# Misc.net
KiCad netlist of a schematic drawn in Altium Designer
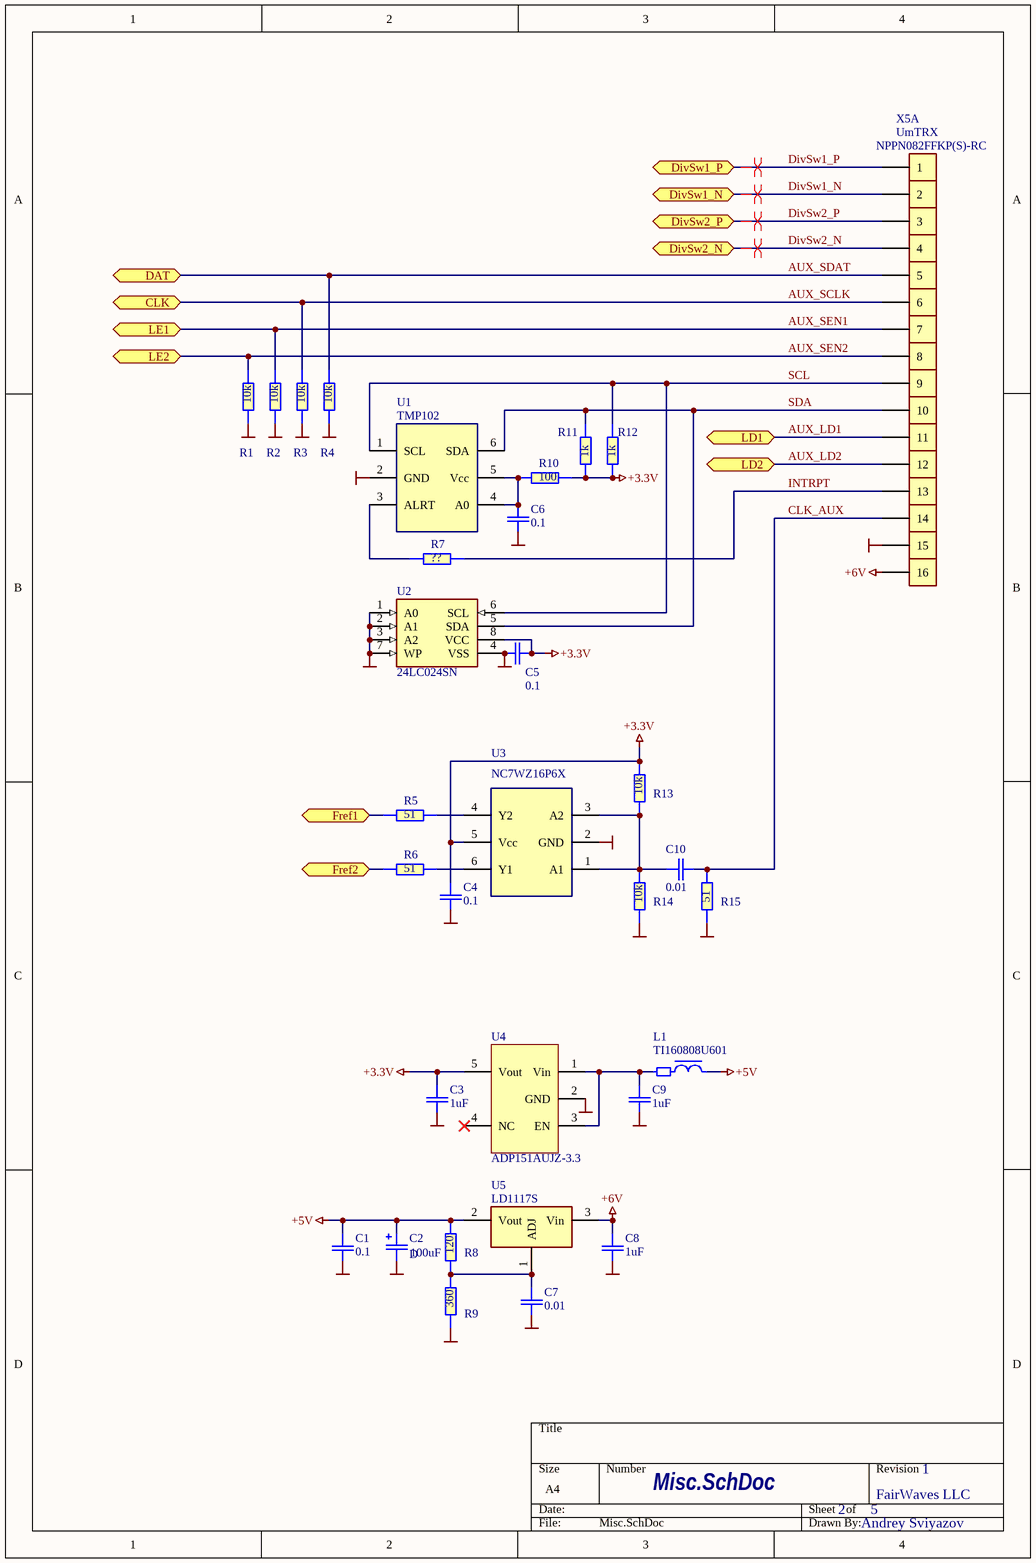
[diagram p0: Misc.SchDoc]

(export (version "E")
  (design (tool "Eeschema 10.0.6"))
  (components
    (comp (ref "C1")
      (value "0.1")
      (footprint "C0603-Phillips")
      (description "Capacitor")
      (fields (field (name "MANUFACTURER") "MURATA") (field (name "TOLERANCE") "20%"))
      (libsource (lib "Capacitors") (part "C0603"))
    )
    (comp (ref "C2")
      (value "100uF")
      (footprint "cd7343")
      (description "Capacitor")
      (fields (field (name "MANUFACTURER") "SPRAGUE"))
      (libsource (lib "altium-import") (part "root_0_mirrored_CD7343_"))
    )
    (comp (ref "C3")
      (value "1uF")
      (footprint "C0603-Phillips")
      (description "Capacitor")
      (fields (field (name "MANUFACTURER") "MURATA") (field (name "TOLERANCE") "20%"))
      (libsource (lib "Capacitors") (part "C0603"))
    )
    (comp (ref "C4")
      (value "0.1")
      (footprint "C0603-Phillips")
      (description "Capacitor")
      (fields (field (name "MANUFACTURER") "MURATA") (field (name "TOLERANCE") "20%"))
      (libsource (lib "Capacitors") (part "C0603"))
    )
    (comp (ref "C5")
      (value "0.1")
      (footprint "C0603-Phillips")
      (description "Capacitor")
      (fields (field (name "MANUFACTURER") "MURATA") (field (name "TOLERANCE") "20%"))
      (libsource (lib "Capacitors") (part "C0603"))
    )
    (comp (ref "C6")
      (value "0.1")
      (footprint "C0603-Phillips")
      (description "Capacitor")
      (fields (field (name "MANUFACTURER") "MURATA") (field (name "TOLERANCE") "20%"))
      (libsource (lib "Capacitors") (part "C0603"))
    )
    (comp (ref "C7")
      (value "0.01")
      (footprint "C0603-Phillips")
      (description "Capacitor")
      (fields (field (name "MANUFACTURER") "MURATA") (field (name "TOLERANCE") "20%"))
      (libsource (lib "Capacitors") (part "C0603"))
    )
    (comp (ref "C8")
      (value "1uF")
      (footprint "C0603-Phillips")
      (description "Capacitor")
      (fields (field (name "MANUFACTURER") "MURATA") (field (name "TOLERANCE") "20%"))
      (libsource (lib "Capacitors") (part "C0603"))
    )
    (comp (ref "C9")
      (value "1uF")
      (footprint "C0603-Phillips")
      (description "Capacitor")
      (fields (field (name "MANUFACTURER") "MURATA") (field (name "TOLERANCE") "20%"))
      (libsource (lib "Capacitors") (part "C0603"))
    )
    (comp (ref "C10")
      (value "0.01")
      (footprint "C0603-Phillips")
      (description "Capacitor")
      (fields (field (name "MANUFACTURER") "MURATA") (field (name "TOLERANCE") "20%"))
      (libsource (lib "Capacitors") (part "C0603"))
    )
    (comp (ref "L1")
      (value "TI160808U601")
      (footprint "Andy:Ti160808-Phillips")
      (description "Choke")
      (fields (field (name "MANUFACTURER") "MURATA"))
      (libsource (lib "altium-import") (part "root_0_mirrored_TI160808_"))
    )
    (comp (ref "R1")
      (value "10k")
      (footprint "R0603-PHILLIPS")
      (description "Resistor")
      (fields (field (name "MANUFACTURER") "YAGEO") (field (name "TOLERANCE") "5%"))
      (libsource (lib "altium-import") (part "root_2_R0603_"))
    )
    (comp (ref "R2")
      (value "10k")
      (footprint "R0603-PHILLIPS")
      (description "Resistor")
      (fields (field (name "MANUFACTURER") "YAGEO") (field (name "TOLERANCE") "5%"))
      (libsource (lib "altium-import") (part "root_2_R0603_"))
    )
    (comp (ref "R3")
      (value "10k")
      (footprint "R0603-PHILLIPS")
      (description "Resistor")
      (fields (field (name "MANUFACTURER") "YAGEO") (field (name "TOLERANCE") "5%"))
      (libsource (lib "altium-import") (part "root_2_R0603_"))
    )
    (comp (ref "R4")
      (value "10k")
      (footprint "R0603-PHILLIPS")
      (description "Resistor")
      (fields (field (name "MANUFACTURER") "YAGEO") (field (name "TOLERANCE") "5%"))
      (libsource (lib "altium-import") (part "root_2_R0603_"))
    )
    (comp (ref "R5")
      (value "51")
      (footprint "R0603-PHILLIPS")
      (description "Resistor")
      (fields (field (name "MANUFACTURER") "YAGEO") (field (name "TOLERANCE") "5%"))
      (libsource (lib "altium-import") (part "root_1_R0603_"))
    )
    (comp (ref "R6")
      (value "51")
      (footprint "R0603-PHILLIPS")
      (description "Resistor")
      (fields (field (name "MANUFACTURER") "YAGEO") (field (name "TOLERANCE") "5%"))
      (libsource (lib "altium-import") (part "root_1_R0603_"))
    )
    (comp (ref "R7")
      (value "??")
      (footprint "R0603-PHILLIPS")
      (description "Resistor")
      (fields (field (name "MANUFACTURER") "YAGEO") (field (name "TOLERANCE") "5%"))
      (libsource (lib "altium-import") (part "root_1_R0603_"))
    )
    (comp (ref "R8")
      (value "120")
      (footprint "R0603-PHILLIPS")
      (description "Resistor")
      (fields (field (name "MANUFACTURER") "YAGEO") (field (name "TOLERANCE") "5%"))
      (libsource (lib "altium-import") (part "root_0_mirrored_R0603_"))
    )
    (comp (ref "R9")
      (value "360")
      (footprint "R0603-PHILLIPS")
      (description "Resistor")
      (fields (field (name "MANUFACTURER") "YAGEO") (field (name "TOLERANCE") "5%"))
      (libsource (lib "altium-import") (part "root_0_mirrored_R0603_"))
    )
    (comp (ref "R10")
      (value "100")
      (footprint "R0603-PHILLIPS")
      (description "Resistor")
      (fields (field (name "MANUFACTURER") "YAGEO") (field (name "TOLERANCE") "5%"))
      (libsource (lib "altium-import") (part "root_1_R0603_"))
    )
    (comp (ref "R11")
      (value "1k")
      (footprint "R0603-PHILLIPS")
      (description "Resistor")
      (fields (field (name "MANUFACTURER") "YAGEO") (field (name "TOLERANCE") "5%"))
      (libsource (lib "altium-import") (part "root_2_R0603_"))
    )
    (comp (ref "R12")
      (value "1k")
      (footprint "R0603-PHILLIPS")
      (description "Resistor")
      (fields (field (name "MANUFACTURER") "YAGEO") (field (name "TOLERANCE") "5%"))
      (libsource (lib "altium-import") (part "root_2_R0603_"))
    )
    (comp (ref "R13")
      (value "10k")
      (footprint "R0603-PHILLIPS")
      (description "Resistor")
      (fields (field (name "MANUFACTURER") "YAGEO") (field (name "TOLERANCE") "5%"))
      (libsource (lib "altium-import") (part "root_0_mirrored_R0603_"))
    )
    (comp (ref "R14")
      (value "10k")
      (footprint "R0603-PHILLIPS")
      (description "Resistor")
      (fields (field (name "MANUFACTURER") "YAGEO") (field (name "TOLERANCE") "5%"))
      (libsource (lib "altium-import") (part "root_0_mirrored_R0603_"))
    )
    (comp (ref "R15")
      (value "51")
      (footprint "R0603-PHILLIPS")
      (description "Resistor")
      (fields (field (name "MANUFACTURER") "YAGEO") (field (name "TOLERANCE") "5%"))
      (libsource (lib "altium-import") (part "root_0_mirrored_R0603_"))
    )
    (comp (ref "U1")
      (value "TMP102")
      (footprint "PDSO-G6")
      (description "IC")
      (fields (field (name "MANUFACTURER") "TI"))
      (libsource (lib "Andy") (part "TMP102"))
    )
    (comp (ref "U2")
      (value "24LC024SN")
      (footprint "FootSO-DIP:SOIC8")
      (description "EEPROM")
      (fields (field (name "MANUFACTURER") "Microchip"))
      (libsource (lib "MicroCircuits0-L") (part "AT24CXX"))
    )
    (comp (ref "U3")
      (value "NC7WZ16P6X")
      (footprint "SC70-6LD(SOT363)")
      (description "IC")
      (fields (field (name "MANUFACTURER") "Fairchild"))
      (libsource (lib "Andy") (part "NC7WZ16P6X"))
    )
    (comp (ref "U4")
      (value "ADP151AUJZ-3.3")
      (footprint "SOT-23-5[3.1x1.8/0.95]")
      (description "IC")
      (fields (field (name "MANUFACTURER") "AD"))
      (libsource (lib "Andy") (part "ADP151AUJZ"))
    )
    (comp (ref "U5")
      (value "LD1117S")
      (footprint "Foot3-4pins:SOT-223-1")
      (description "IC")
      (fields (field (name "MANUFACTURER") "STMicro"))
      (libsource (lib "altium-import") (part "root_0_mirrored_LD1117ADJ_"))
    )
    (comp (ref "X5")
      (value "NPPN082FFKP(S)-RC")
      (footprint "NPPN082FFKP(S)")
      (description "Connector female 2mm SMD")
      (fields (field (name "MANUFACTURER") "Sullins") (field (name "MISC") "UmTRX"))
      (libsource (lib "Andy") (part "NPPN082FFKP(S)"))
    )
  )
  (nets
    (net (code "1") (name "+3.3V") (class "Default")
      (node (ref "C3") (pin "2") (pinfunction "2_2") (pintype "passive"))
      (node (ref "C4") (pin "2") (pinfunction "2_2") (pintype "passive"))
      (node (ref "C5") (pin "2") (pinfunction "2_2") (pintype "passive"))
      (node (ref "R10") (pin "2") (pinfunction "2_2") (pintype "passive"))
      (node (ref "R11") (pin "1") (pinfunction "1_1") (pintype "passive"))
      (node (ref "R12") (pin "1") (pinfunction "1_1") (pintype "passive"))
      (node (ref "R13") (pin "1") (pinfunction "1_1") (pintype "passive"))
      (node (ref "U2") (pin "8") (pinfunction "VCC_8") (pintype "power_in"))
      (node (ref "U3") (pin "5") (pinfunction "Vcc_5") (pintype "passive"))
      (node (ref "U4") (pin "5") (pinfunction "Vout_5") (pintype "passive"))
    )
    (net (code "2") (name "+5V") (class "Default")
      (node (ref "C1") (pin "2") (pinfunction "2_2") (pintype "passive"))
      (node (ref "C2") (pin "1") (pinfunction "+_1") (pintype "passive"))
      (node (ref "L1") (pin "1") (pinfunction "1_1") (pintype "passive"))
      (node (ref "R8") (pin "1") (pinfunction "1_1") (pintype "passive"))
      (node (ref "U5") (pin "2") (pinfunction "Vout_2") (pintype "passive"))
    )
    (net (code "3") (name "+6V") (class "Default")
      (node (ref "C8") (pin "2") (pinfunction "2_2") (pintype "passive"))
      (node (ref "U5") (pin "3") (pinfunction "Vin_3") (pintype "passive"))
      (node (ref "X5") (pin "16") (pinfunction "16_16") (pintype "passive"))
    )
    (net (code "4") (name "/AUX_LD1") (class "Default")
      (node (ref "X5") (pin "11") (pinfunction "11_11") (pintype "passive"))
    )
    (net (code "5") (name "/AUX_LD2") (class "Default")
      (node (ref "X5") (pin "12") (pinfunction "12_12") (pintype "passive"))
    )
    (net (code "6") (name "/AUX_SCLK") (class "Default")
      (node (ref "R3") (pin "2") (pinfunction "2_2") (pintype "passive"))
      (node (ref "X5") (pin "6") (pinfunction "6_6") (pintype "passive"))
    )
    (net (code "7") (name "/AUX_SDAT") (class "Default")
      (node (ref "R4") (pin "2") (pinfunction "2_2") (pintype "passive"))
      (node (ref "X5") (pin "5") (pinfunction "5_5") (pintype "passive"))
    )
    (net (code "8") (name "/AUX_SEN1") (class "Default")
      (node (ref "R2") (pin "2") (pinfunction "2_2") (pintype "passive"))
      (node (ref "X5") (pin "7") (pinfunction "7_7") (pintype "passive"))
    )
    (net (code "9") (name "/AUX_SEN2") (class "Default")
      (node (ref "R1") (pin "2") (pinfunction "2_2") (pintype "passive"))
      (node (ref "X5") (pin "8") (pinfunction "8_8") (pintype "passive"))
    )
    (net (code "10") (name "/CLK_AUX") (class "Default")
      (node (ref "C10") (pin "1") (pinfunction "1_1") (pintype "passive"))
      (node (ref "R15") (pin "1") (pinfunction "1_1") (pintype "passive"))
      (node (ref "X5") (pin "14") (pinfunction "14_14") (pintype "passive"))
    )
    (net (code "11") (name "/DivSw1_N") (class "Default")
      (node (ref "X5") (pin "2") (pinfunction "2_2") (pintype "passive"))
    )
    (net (code "12") (name "/DivSw1_P") (class "Default")
      (node (ref "X5") (pin "1") (pinfunction "1_1") (pintype "passive"))
    )
    (net (code "13") (name "/DivSw2_N") (class "Default")
      (node (ref "X5") (pin "4") (pinfunction "4_4") (pintype "passive"))
    )
    (net (code "14") (name "/DivSw2_P") (class "Default")
      (node (ref "X5") (pin "3") (pinfunction "3_3") (pintype "passive"))
    )
    (net (code "15") (name "/Fref1") (class "Default")
      (node (ref "R5") (pin "1") (pinfunction "1_1") (pintype "passive"))
    )
    (net (code "16") (name "/Fref2") (class "Default")
      (node (ref "R6") (pin "1") (pinfunction "1_1") (pintype "passive"))
    )
    (net (code "17") (name "/INTRPT") (class "Default")
      (node (ref "R7") (pin "2") (pinfunction "2_2") (pintype "passive"))
      (node (ref "X5") (pin "13") (pinfunction "13_13") (pintype "passive"))
    )
    (net (code "18") (name "/SCL") (class "Default")
      (node (ref "R12") (pin "2") (pinfunction "2_2") (pintype "passive"))
      (node (ref "U1") (pin "1") (pinfunction "SCL_1") (pintype "passive"))
      (node (ref "U2") (pin "6") (pinfunction "SCL_6") (pintype "input"))
      (node (ref "X5") (pin "9") (pinfunction "9_9") (pintype "passive"))
    )
    (net (code "19") (name "/SDA") (class "Default")
      (node (ref "R11") (pin "2") (pinfunction "2_2") (pintype "passive"))
      (node (ref "U1") (pin "6") (pinfunction "SDA_6") (pintype "passive"))
      (node (ref "U2") (pin "5") (pinfunction "SDA_5") (pintype "passive"))
      (node (ref "X5") (pin "10") (pinfunction "10_10") (pintype "passive"))
    )
    (net (code "20") (name "GND") (class "Default")
      (node (ref "C1") (pin "1") (pinfunction "1_1") (pintype "passive"))
      (node (ref "C2") (pin "2") (pinfunction "-_2") (pintype "passive"))
      (node (ref "C3") (pin "1") (pinfunction "1_1") (pintype "passive"))
      (node (ref "C4") (pin "1") (pinfunction "1_1") (pintype "passive"))
      (node (ref "C5") (pin "1") (pinfunction "1_1") (pintype "passive"))
      (node (ref "C6") (pin "1") (pinfunction "1_1") (pintype "passive"))
      (node (ref "C7") (pin "1") (pinfunction "1_1") (pintype "passive"))
      (node (ref "C8") (pin "1") (pinfunction "1_1") (pintype "passive"))
      (node (ref "C9") (pin "1") (pinfunction "1_1") (pintype "passive"))
      (node (ref "R1") (pin "1") (pinfunction "1_1") (pintype "passive"))
      (node (ref "R14") (pin "2") (pinfunction "2_2") (pintype "passive"))
      (node (ref "R15") (pin "2") (pinfunction "2_2") (pintype "passive"))
      (node (ref "R2") (pin "1") (pinfunction "1_1") (pintype "passive"))
      (node (ref "R3") (pin "1") (pinfunction "1_1") (pintype "passive"))
      (node (ref "R4") (pin "1") (pinfunction "1_1") (pintype "passive"))
      (node (ref "R9") (pin "2") (pinfunction "2_2") (pintype "passive"))
      (node (ref "U1") (pin "2") (pinfunction "GND_2") (pintype "passive"))
      (node (ref "U2") (pin "1") (pinfunction "A0_1") (pintype "input"))
      (node (ref "U2") (pin "2") (pinfunction "A1_2") (pintype "input"))
      (node (ref "U2") (pin "3") (pinfunction "A2_3") (pintype "input"))
      (node (ref "U2") (pin "4") (pinfunction "VSS_4") (pintype "power_in"))
      (node (ref "U2") (pin "7") (pinfunction "WP_7") (pintype "input"))
      (node (ref "U3") (pin "2") (pinfunction "GND_2") (pintype "passive"))
      (node (ref "U4") (pin "2") (pinfunction "GND_2") (pintype "passive"))
      (node (ref "X5") (pin "15") (pinfunction "15_15") (pintype "passive"))
    )
    (net (code "21") (name "Net-(U1-A0)") (class "Default")
      (node (ref "C6") (pin "2") (pinfunction "2_2") (pintype "passive"))
      (node (ref "R10") (pin "1") (pinfunction "1_1") (pintype "passive"))
      (node (ref "U1") (pin "4") (pinfunction "A0_4") (pintype "passive"))
      (node (ref "U1") (pin "5") (pinfunction "Vcc_5") (pintype "passive"))
    )
    (net (code "22") (name "Net-(U1-ALRT)") (class "Default")
      (node (ref "R7") (pin "1") (pinfunction "1_1") (pintype "passive"))
      (node (ref "U1") (pin "3") (pinfunction "ALRT_3") (pintype "passive"))
    )
    (net (code "23") (name "Net-(U3-A1)") (class "Default")
      (node (ref "C10") (pin "2") (pinfunction "2_2") (pintype "passive"))
      (node (ref "R13") (pin "2") (pinfunction "2_2") (pintype "passive"))
      (node (ref "R14") (pin "1") (pinfunction "1_1") (pintype "passive"))
      (node (ref "U3") (pin "1") (pinfunction "A1_1") (pintype "passive"))
      (node (ref "U3") (pin "3") (pinfunction "A2_3") (pintype "passive"))
    )
    (net (code "24") (name "Net-(U3-Y1)") (class "Default")
      (node (ref "R6") (pin "2") (pinfunction "2_2") (pintype "passive"))
      (node (ref "U3") (pin "6") (pinfunction "Y1_6") (pintype "passive"))
    )
    (net (code "25") (name "Net-(U3-Y2)") (class "Default")
      (node (ref "R5") (pin "2") (pinfunction "2_2") (pintype "passive"))
      (node (ref "U3") (pin "4") (pinfunction "Y2_4") (pintype "passive"))
    )
    (net (code "26") (name "Net-(U4-EN)") (class "Default")
      (node (ref "C9") (pin "2") (pinfunction "2_2") (pintype "passive"))
      (node (ref "L1") (pin "2") (pinfunction "2_2") (pintype "passive"))
      (node (ref "U4") (pin "1") (pinfunction "Vin_1") (pintype "passive"))
      (node (ref "U4") (pin "3") (pinfunction "EN_3") (pintype "passive"))
    )
    (net (code "27") (name "Net-(U5-ADJ)") (class "Default")
      (node (ref "C7") (pin "2") (pinfunction "2_2") (pintype "passive"))
      (node (ref "R8") (pin "2") (pinfunction "2_2") (pintype "passive"))
      (node (ref "R9") (pin "1") (pinfunction "1_1") (pintype "passive"))
      (node (ref "U5") (pin "1") (pinfunction "ADJ_1") (pintype "passive"))
    )
    (net (code "28") (name "unconnected-(U4-NC-Pad4)") (class "Default")
      (node (ref "U4") (pin "4") (pinfunction "NC_4") (pintype "passive+no_connect"))
    )
  )
)
